# design.net
KiCad netlist of a schematic drawn in EAGLE
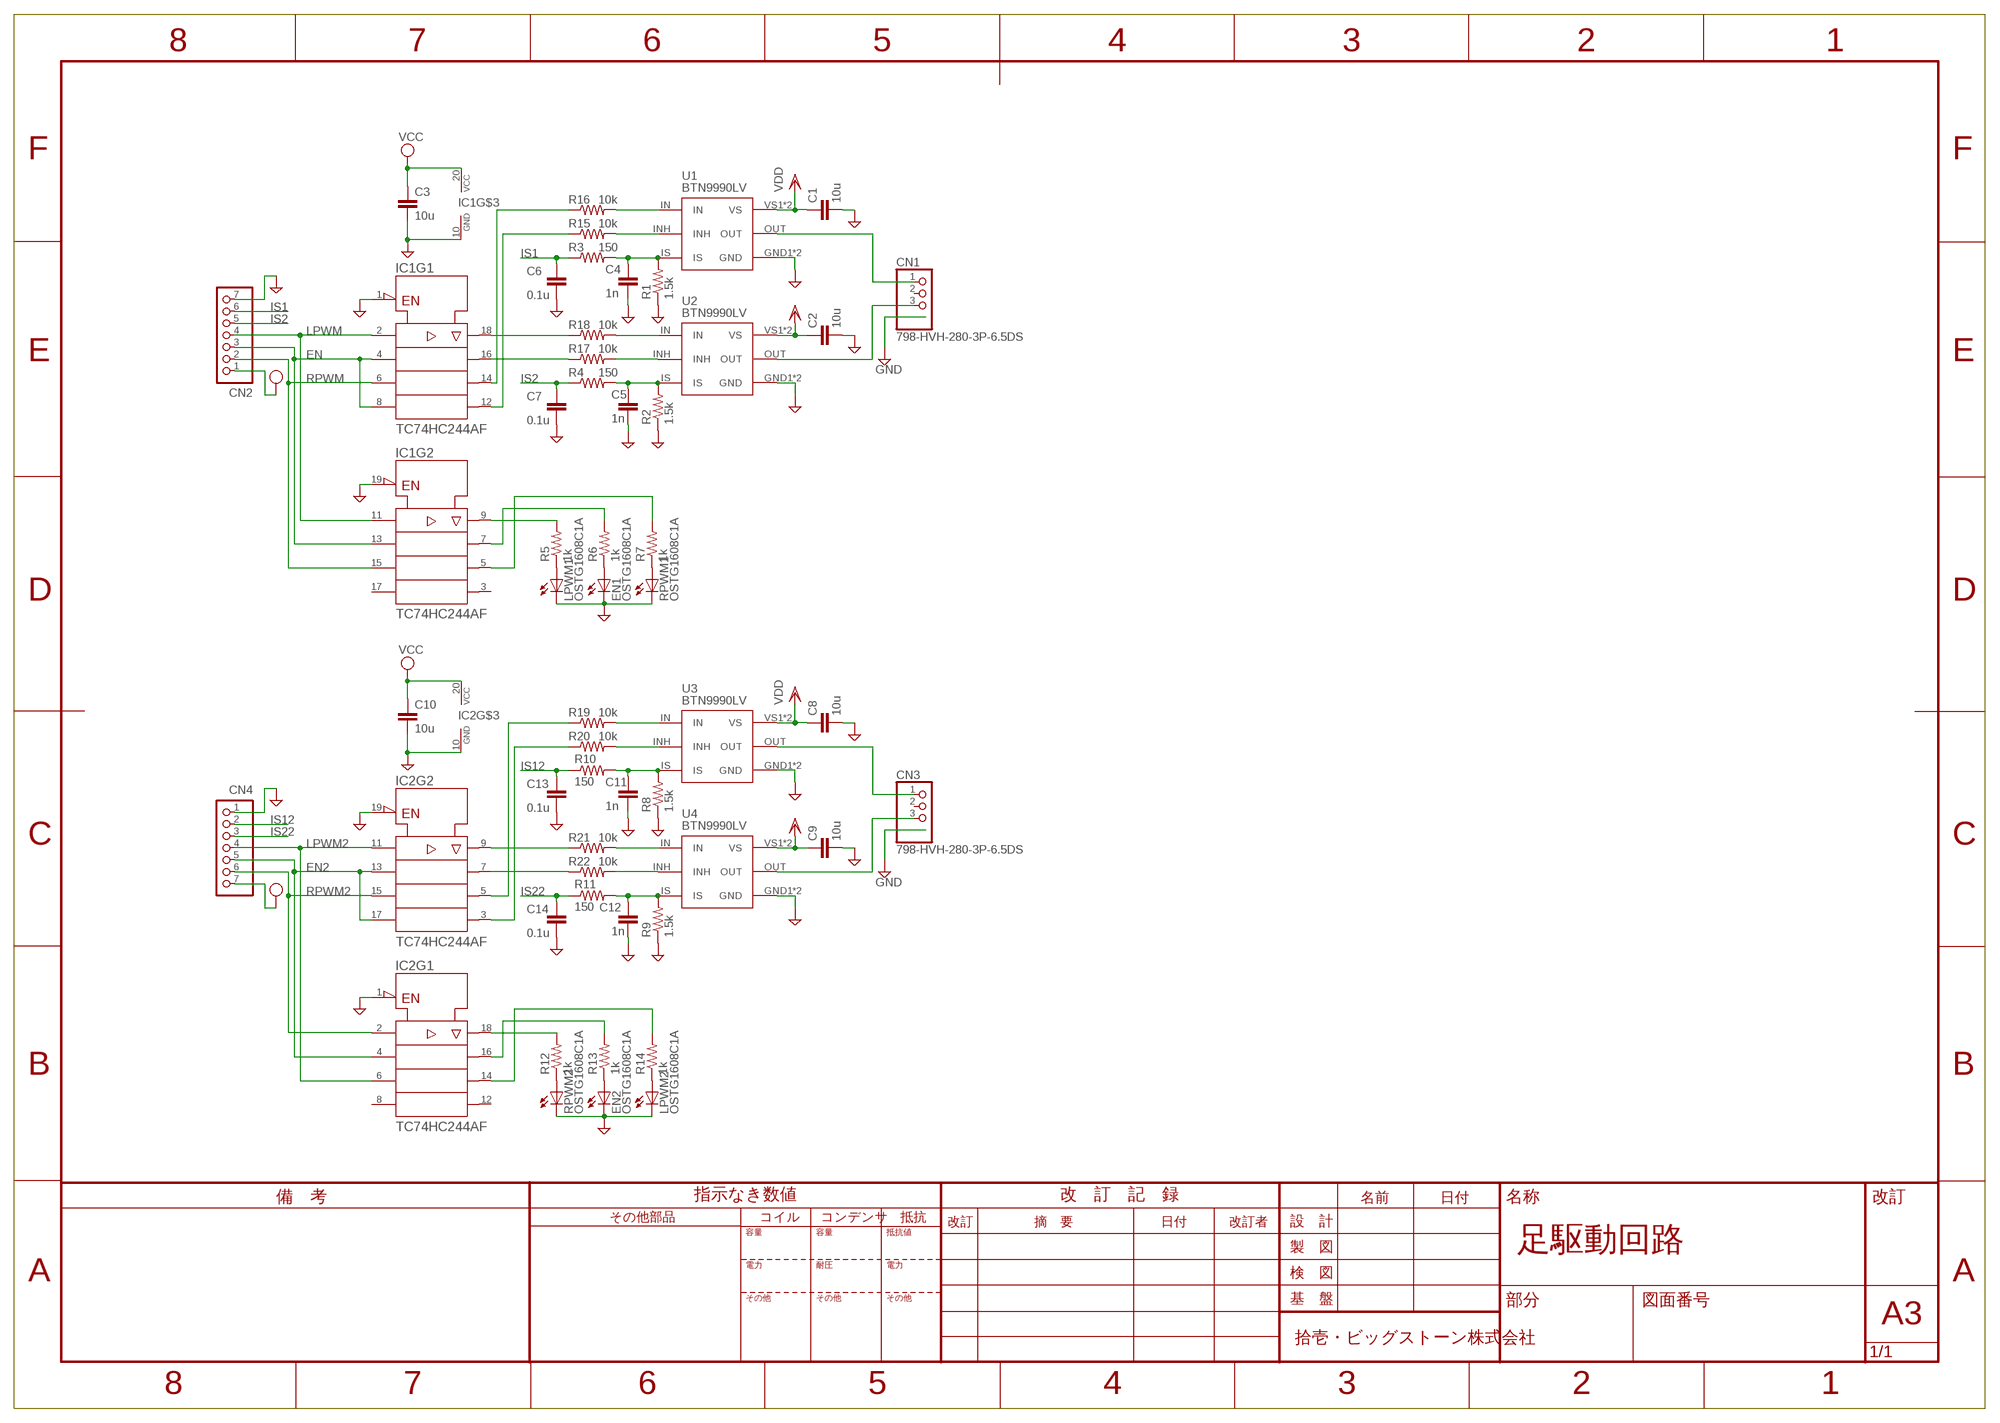
[diagram p0: schematic, sheet 1]

(export (version "E")
  (design (tool "Eeschema 10.0.6"))
  (components
    (comp (ref "C1")
      (value "10u")
      (footprint "eagle-import:C3216")
      (libsource (lib "eagle-import") (part "GCM?31CD71H106KE36K"))
    )
    (comp (ref "C2")
      (value "10u")
      (footprint "eagle-import:C3216")
      (libsource (lib "eagle-import") (part "GCM?31CD71H106KE36K"))
    )
    (comp (ref "C3")
      (value "10u")
      (footprint "eagle-import:C3216")
      (libsource (lib "eagle-import") (part "GCM?31CD71H106KE36K"))
    )
    (comp (ref "C4")
      (value "1n")
      (footprint "eagle-import:C1608")
      (libsource (lib "eagle-import") (part "GCM?188R91H102KA37D"))
    )
    (comp (ref "C5")
      (value "1n")
      (footprint "eagle-import:C1608")
      (libsource (lib "eagle-import") (part "GCM?188R91H102KA37D"))
    )
    (comp (ref "C6")
      (value "0.1u")
      (footprint "eagle-import:C1608")
      (libsource (lib "eagle-import") (part "GCM?188L81H104KA57D"))
    )
    (comp (ref "C7")
      (value "0.1u")
      (footprint "eagle-import:C1608")
      (libsource (lib "eagle-import") (part "GCM?188L81H104KA57D"))
    )
    (comp (ref "C8")
      (value "10u")
      (footprint "eagle-import:C3216")
      (libsource (lib "eagle-import") (part "GCM?31CD71H106KE36K"))
    )
    (comp (ref "C9")
      (value "10u")
      (footprint "eagle-import:C3216")
      (libsource (lib "eagle-import") (part "GCM?31CD71H106KE36K"))
    )
    (comp (ref "C10")
      (value "10u")
      (footprint "eagle-import:C3216")
      (libsource (lib "eagle-import") (part "GCM?31CD71H106KE36K"))
    )
    (comp (ref "C11")
      (value "1n")
      (footprint "eagle-import:C1608")
      (libsource (lib "eagle-import") (part "GCM?188R91H102KA37D"))
    )
    (comp (ref "C12")
      (value "1n")
      (footprint "eagle-import:C1608")
      (libsource (lib "eagle-import") (part "GCM?188R91H102KA37D"))
    )
    (comp (ref "C13")
      (value "0.1u")
      (footprint "eagle-import:C1608")
      (libsource (lib "eagle-import") (part "GCM?188L81H104KA57D"))
    )
    (comp (ref "C14")
      (value "0.1u")
      (footprint "eagle-import:C1608")
      (libsource (lib "eagle-import") (part "GCM?188L81H104KA57D"))
    )
    (comp (ref "CN1")
      (value "798-HVH-280-3P-6.5DS")
      (footprint "eagle-import:798-HVH-280-3P-6.5DS")
      (libsource (lib "eagle-import") (part "798-HVH-280-3P-6.5DS"))
    )
    (comp (ref "CN2")
      (value "B7B-XH-A")
      (footprint "eagle-import:B7B-XH-A")
      (libsource (lib "eagle-import") (part "B7B-XH-A"))
    )
    (comp (ref "CN3")
      (value "798-HVH-280-3P-6.5DS")
      (footprint "eagle-import:798-HVH-280-3P-6.5DS")
      (libsource (lib "eagle-import") (part "798-HVH-280-3P-6.5DS"))
    )
    (comp (ref "CN4")
      (value "B7B-XH-A")
      (footprint "eagle-import:B7B-XH-A")
      (libsource (lib "eagle-import") (part "B7B-XH-A"))
    )
    (comp (ref "EN1")
      (value "OSTG1608C1A")
      (footprint "eagle-import:LEDC1608X39N_G")
      (libsource (lib "eagle-import") (part "OSTG1608C1A"))
    )
    (comp (ref "EN2")
      (value "OSTG1608C1A")
      (footprint "eagle-import:LEDC1608X39N_G")
      (libsource (lib "eagle-import") (part "OSTG1608C1A"))
    )
    (comp (ref "IC1")
      (value "TC74HC244AF")
      (footprint "eagle-import:SOP20")
      (libsource (lib "eagle-import") (part "TC74HC244AF"))
    )
    (comp (ref "IC2")
      (value "TC74HC244AF")
      (footprint "eagle-import:SOP20")
      (libsource (lib "eagle-import") (part "TC74HC244AF"))
    )
    (comp (ref "LPWM1")
      (value "OSTG1608C1A")
      (footprint "eagle-import:LEDC1608X39N_G")
      (libsource (lib "eagle-import") (part "OSTG1608C1A"))
    )
    (comp (ref "LPWM2")
      (value "OSTG1608C1A")
      (footprint "eagle-import:LEDC1608X39N_G")
      (libsource (lib "eagle-import") (part "OSTG1608C1A"))
    )
    (comp (ref "R1")
      (value "1.5k")
      (footprint "eagle-import:R0603")
      (libsource (lib "eagle-import") (part "R1608"))
    )
    (comp (ref "R2")
      (value "1.5k")
      (footprint "eagle-import:R0603")
      (libsource (lib "eagle-import") (part "R1608"))
    )
    (comp (ref "R3")
      (value "150")
      (footprint "eagle-import:R0603")
      (libsource (lib "eagle-import") (part "R1608"))
    )
    (comp (ref "R4")
      (value "150")
      (footprint "eagle-import:R0603")
      (libsource (lib "eagle-import") (part "R1608"))
    )
    (comp (ref "R5")
      (value "1k")
      (footprint "eagle-import:R0603")
      (libsource (lib "eagle-import") (part "R1608"))
    )
    (comp (ref "R6")
      (value "1k")
      (footprint "eagle-import:R0603")
      (libsource (lib "eagle-import") (part "R1608"))
    )
    (comp (ref "R7")
      (value "1k")
      (footprint "eagle-import:R0603")
      (libsource (lib "eagle-import") (part "R1608"))
    )
    (comp (ref "R8")
      (value "1.5k")
      (footprint "eagle-import:R0603")
      (libsource (lib "eagle-import") (part "R1608"))
    )
    (comp (ref "R9")
      (value "1.5k")
      (footprint "eagle-import:R0603")
      (libsource (lib "eagle-import") (part "R1608"))
    )
    (comp (ref "R10")
      (value "150")
      (footprint "eagle-import:R0603")
      (libsource (lib "eagle-import") (part "R1608"))
    )
    (comp (ref "R11")
      (value "150")
      (footprint "eagle-import:R0603")
      (libsource (lib "eagle-import") (part "R1608"))
    )
    (comp (ref "R12")
      (value "1k")
      (footprint "eagle-import:R0603")
      (libsource (lib "eagle-import") (part "R1608"))
    )
    (comp (ref "R13")
      (value "1k")
      (footprint "eagle-import:R0603")
      (libsource (lib "eagle-import") (part "R1608"))
    )
    (comp (ref "R14")
      (value "1k")
      (footprint "eagle-import:R0603")
      (libsource (lib "eagle-import") (part "R1608"))
    )
    (comp (ref "R15")
      (value "10k")
      (footprint "eagle-import:R1608")
      (libsource (lib "eagle-import") (part "RC0603J10K"))
    )
    (comp (ref "R16")
      (value "10k")
      (footprint "eagle-import:R1608")
      (libsource (lib "eagle-import") (part "RC0603J10K"))
    )
    (comp (ref "R17")
      (value "10k")
      (footprint "eagle-import:R1608")
      (libsource (lib "eagle-import") (part "RC0603J10K"))
    )
    (comp (ref "R18")
      (value "10k")
      (footprint "eagle-import:R1608")
      (libsource (lib "eagle-import") (part "RC0603J10K"))
    )
    (comp (ref "R19")
      (value "10k")
      (footprint "eagle-import:R1608")
      (libsource (lib "eagle-import") (part "RC0603J10K"))
    )
    (comp (ref "R20")
      (value "10k")
      (footprint "eagle-import:R1608")
      (libsource (lib "eagle-import") (part "RC0603J10K"))
    )
    (comp (ref "R21")
      (value "10k")
      (footprint "eagle-import:R1608")
      (libsource (lib "eagle-import") (part "RC0603J10K"))
    )
    (comp (ref "R22")
      (value "10k")
      (footprint "eagle-import:R1608")
      (libsource (lib "eagle-import") (part "RC0603J10K"))
    )
    (comp (ref "RPWM1")
      (value "OSTG1608C1A")
      (footprint "eagle-import:LEDC1608X39N_G")
      (libsource (lib "eagle-import") (part "OSTG1608C1A"))
    )
    (comp (ref "RPWM2")
      (value "OSTG1608C1A")
      (footprint "eagle-import:LEDC1608X39N_G")
      (libsource (lib "eagle-import") (part "OSTG1608C1A"))
    )
    (comp (ref "U1")
      (value "BTN9990LV")
      (footprint "eagle-import:BTN9990LV")
      (libsource (lib "eagle-import") (part "BTN9990LV"))
    )
    (comp (ref "U2")
      (value "BTN9990LV")
      (footprint "eagle-import:BTN9990LV")
      (libsource (lib "eagle-import") (part "BTN9990LV"))
    )
    (comp (ref "U3")
      (value "BTN9990LV")
      (footprint "eagle-import:BTN9990LV")
      (libsource (lib "eagle-import") (part "BTN9990LV"))
    )
    (comp (ref "U4")
      (value "BTN9990LV")
      (footprint "eagle-import:BTN9990LV")
      (libsource (lib "eagle-import") (part "BTN9990LV"))
    )
  )
  (nets
    (net (code "1") (name "/EN") (class "Default")
      (node (ref "CN2") (pin "3") (pinfunction "3_3") (pintype "passive"))
      (node (ref "IC1") (pin "13") (pinfunction "A2_13") (pintype "input"))
      (node (ref "IC1") (pin "4") (pinfunction "A2_4") (pintype "input"))
      (node (ref "IC1") (pin "8") (pinfunction "A4_8") (pintype "input"))
    )
    (net (code "2") (name "/EN2") (class "Default")
      (node (ref "CN4") (pin "5") (pinfunction "5_5") (pintype "passive"))
      (node (ref "IC2") (pin "13") (pinfunction "A2_13") (pintype "input"))
      (node (ref "IC2") (pin "17") (pinfunction "A4_17") (pintype "input"))
      (node (ref "IC2") (pin "4") (pinfunction "A2_4") (pintype "input"))
    )
    (net (code "3") (name "/IS1") (class "Default")
      (node (ref "C6") (pin "1") (pinfunction "1_1") (pintype "passive"))
      (node (ref "CN2") (pin "6") (pinfunction "6_6") (pintype "passive"))
      (node (ref "R3") (pin "1") (pinfunction "1_1") (pintype "passive"))
    )
    (net (code "4") (name "/IS2") (class "Default")
      (node (ref "C7") (pin "1") (pinfunction "1_1") (pintype "passive"))
      (node (ref "CN2") (pin "5") (pinfunction "5_5") (pintype "passive"))
      (node (ref "R4") (pin "1") (pinfunction "1_1") (pintype "passive"))
    )
    (net (code "5") (name "/IS12") (class "Default")
      (node (ref "C13") (pin "1") (pinfunction "1_1") (pintype "passive"))
      (node (ref "CN4") (pin "2") (pinfunction "2_2") (pintype "passive"))
      (node (ref "R10") (pin "1") (pinfunction "1_1") (pintype "passive"))
    )
    (net (code "6") (name "/IS22") (class "Default")
      (node (ref "C14") (pin "1") (pinfunction "1_1") (pintype "passive"))
      (node (ref "CN4") (pin "3") (pinfunction "3_3") (pintype "passive"))
      (node (ref "R11") (pin "1") (pinfunction "1_1") (pintype "passive"))
    )
    (net (code "7") (name "/LPWM") (class "Default")
      (node (ref "CN2") (pin "4") (pinfunction "4_4") (pintype "passive"))
      (node (ref "IC1") (pin "11") (pinfunction "A1_11") (pintype "input"))
      (node (ref "IC1") (pin "2") (pinfunction "A1_2") (pintype "input"))
    )
    (net (code "8") (name "/LPWM2") (class "Default")
      (node (ref "CN4") (pin "4") (pinfunction "4_4") (pintype "passive"))
      (node (ref "IC2") (pin "11") (pinfunction "A1_11") (pintype "input"))
      (node (ref "IC2") (pin "6") (pinfunction "A3_6") (pintype "input"))
    )
    (net (code "9") (name "/RPWM") (class "Default")
      (node (ref "CN2") (pin "2") (pinfunction "2_2") (pintype "passive"))
      (node (ref "IC1") (pin "15") (pinfunction "A3_15") (pintype "input"))
      (node (ref "IC1") (pin "6") (pinfunction "A3_6") (pintype "input"))
    )
    (net (code "10") (name "/RPWM2") (class "Default")
      (node (ref "CN4") (pin "6") (pinfunction "6_6") (pintype "passive"))
      (node (ref "IC2") (pin "15") (pinfunction "A3_15") (pintype "input"))
      (node (ref "IC2") (pin "2") (pinfunction "A1_2") (pintype "input"))
    )
    (net (code "11") (name "GND") (class "Default")
      (node (ref "C1") (pin "2") (pinfunction "2_2") (pintype "passive"))
      (node (ref "C10") (pin "2") (pinfunction "2_2") (pintype "passive"))
      (node (ref "C11") (pin "2") (pinfunction "2_2") (pintype "passive"))
      (node (ref "C12") (pin "2") (pinfunction "2_2") (pintype "passive"))
      (node (ref "C13") (pin "2") (pinfunction "2_2") (pintype "passive"))
      (node (ref "C14") (pin "2") (pinfunction "2_2") (pintype "passive"))
      (node (ref "C2") (pin "2") (pinfunction "2_2") (pintype "passive"))
      (node (ref "C3") (pin "2") (pinfunction "2_2") (pintype "passive"))
      (node (ref "C4") (pin "2") (pinfunction "2_2") (pintype "passive"))
      (node (ref "C5") (pin "2") (pinfunction "2_2") (pintype "passive"))
      (node (ref "C6") (pin "2") (pinfunction "2_2") (pintype "passive"))
      (node (ref "C7") (pin "2") (pinfunction "2_2") (pintype "passive"))
      (node (ref "C8") (pin "2") (pinfunction "2_2") (pintype "passive"))
      (node (ref "C9") (pin "2") (pinfunction "2_2") (pintype "passive"))
      (node (ref "CN1") (pin "P$1") (pinfunction "P$1_P$1") (pintype "bidirectional"))
      (node (ref "CN1") (pin "P$2") (pinfunction "P$1_P$2") (pintype "bidirectional"))
      (node (ref "CN1") (pin "P$3") (pinfunction "P$1_P$3") (pintype "bidirectional"))
      (node (ref "CN1") (pin "P$4") (pinfunction "P$1_P$4") (pintype "bidirectional"))
      (node (ref "CN2") (pin "7") (pinfunction "7_7") (pintype "passive"))
      (node (ref "CN3") (pin "P$1") (pinfunction "P$1_P$1") (pintype "bidirectional"))
      (node (ref "CN3") (pin "P$2") (pinfunction "P$1_P$2") (pintype "bidirectional"))
      (node (ref "CN3") (pin "P$3") (pinfunction "P$1_P$3") (pintype "bidirectional"))
      (node (ref "CN3") (pin "P$4") (pinfunction "P$1_P$4") (pintype "bidirectional"))
      (node (ref "CN4") (pin "1") (pinfunction "1_1") (pintype "passive"))
      (node (ref "EN1") (pin "K") (pinfunction "C_K") (pintype "passive"))
      (node (ref "EN2") (pin "K") (pinfunction "C_K") (pintype "passive"))
      (node (ref "IC1") (pin "1") (pinfunction "~{G}_1") (pintype "input"))
      (node (ref "IC1") (pin "10") (pinfunction "GND_10") (pintype "power_in"))
      (node (ref "IC1") (pin "19") (pinfunction "~{G}_19") (pintype "input"))
      (node (ref "IC2") (pin "1") (pinfunction "~{G}_1") (pintype "input"))
      (node (ref "IC2") (pin "10") (pinfunction "GND_10") (pintype "power_in"))
      (node (ref "IC2") (pin "19") (pinfunction "~{G}_19") (pintype "input"))
      (node (ref "LPWM1") (pin "K") (pinfunction "C_K") (pintype "passive"))
      (node (ref "LPWM2") (pin "K") (pinfunction "C_K") (pintype "passive"))
      (node (ref "R1") (pin "1") (pinfunction "1_1") (pintype "passive"))
      (node (ref "R2") (pin "1") (pinfunction "1_1") (pintype "passive"))
      (node (ref "R8") (pin "1") (pinfunction "1_1") (pintype "passive"))
      (node (ref "R9") (pin "1") (pinfunction "1_1") (pintype "passive"))
      (node (ref "RPWM1") (pin "K") (pinfunction "C_K") (pintype "passive"))
      (node (ref "RPWM2") (pin "K") (pinfunction "C_K") (pintype "passive"))
      (node (ref "U1") (pin "GND1") (pinfunction "GND_GND1") (pintype "bidirectional"))
      (node (ref "U1") (pin "GND2") (pinfunction "GND_GND2") (pintype "bidirectional"))
      (node (ref "U2") (pin "GND1") (pinfunction "GND_GND1") (pintype "bidirectional"))
      (node (ref "U2") (pin "GND2") (pinfunction "GND_GND2") (pintype "bidirectional"))
      (node (ref "U3") (pin "GND1") (pinfunction "GND_GND1") (pintype "bidirectional"))
      (node (ref "U3") (pin "GND2") (pinfunction "GND_GND2") (pintype "bidirectional"))
      (node (ref "U4") (pin "GND1") (pinfunction "GND_GND1") (pintype "bidirectional"))
      (node (ref "U4") (pin "GND2") (pinfunction "GND_GND2") (pintype "bidirectional"))
    )
    (net (code "12") (name "Net-(C4-Pad1)") (class "Default")
      (node (ref "C4") (pin "1") (pinfunction "1_1") (pintype "passive"))
      (node (ref "R1") (pin "2") (pinfunction "2_2") (pintype "passive"))
      (node (ref "R3") (pin "2") (pinfunction "2_2") (pintype "passive"))
      (node (ref "U1") (pin "IS") (pinfunction "IS_IS") (pintype "bidirectional"))
    )
    (net (code "13") (name "Net-(C5-Pad1)") (class "Default")
      (node (ref "C5") (pin "1") (pinfunction "1_1") (pintype "passive"))
      (node (ref "R2") (pin "2") (pinfunction "2_2") (pintype "passive"))
      (node (ref "R4") (pin "2") (pinfunction "2_2") (pintype "passive"))
      (node (ref "U2") (pin "IS") (pinfunction "IS_IS") (pintype "bidirectional"))
    )
    (net (code "14") (name "Net-(C11-Pad1)") (class "Default")
      (node (ref "C11") (pin "1") (pinfunction "1_1") (pintype "passive"))
      (node (ref "R10") (pin "2") (pinfunction "2_2") (pintype "passive"))
      (node (ref "R8") (pin "2") (pinfunction "2_2") (pintype "passive"))
      (node (ref "U3") (pin "IS") (pinfunction "IS_IS") (pintype "bidirectional"))
    )
    (net (code "15") (name "Net-(C12-Pad1)") (class "Default")
      (node (ref "C12") (pin "1") (pinfunction "1_1") (pintype "passive"))
      (node (ref "R11") (pin "2") (pinfunction "2_2") (pintype "passive"))
      (node (ref "R9") (pin "2") (pinfunction "2_2") (pintype "passive"))
      (node (ref "U4") (pin "IS") (pinfunction "IS_IS") (pintype "bidirectional"))
    )
    (net (code "16") (name "Net-(CN1-Pad1)") (class "Default")
      (node (ref "CN1") (pin "1") (pinfunction "1_1") (pintype "passive"))
      (node (ref "U1") (pin "OUT") (pinfunction "OUT_OUT") (pintype "bidirectional"))
    )
    (net (code "17") (name "Net-(CN1-Pad3)") (class "Default")
      (node (ref "CN1") (pin "3") (pinfunction "3_3") (pintype "passive"))
      (node (ref "U2") (pin "OUT") (pinfunction "OUT_OUT") (pintype "bidirectional"))
    )
    (net (code "18") (name "Net-(CN3-Pad1)") (class "Default")
      (node (ref "CN3") (pin "1") (pinfunction "1_1") (pintype "passive"))
      (node (ref "U3") (pin "OUT") (pinfunction "OUT_OUT") (pintype "bidirectional"))
    )
    (net (code "19") (name "Net-(CN3-Pad3)") (class "Default")
      (node (ref "CN3") (pin "3") (pinfunction "3_3") (pintype "passive"))
      (node (ref "U4") (pin "OUT") (pinfunction "OUT_OUT") (pintype "bidirectional"))
    )
    (net (code "20") (name "Net-(EN1-PadA)") (class "Default")
      (node (ref "EN1") (pin "A") (pinfunction "A_A") (pintype "passive"))
      (node (ref "R6") (pin "1") (pinfunction "1_1") (pintype "passive"))
    )
    (net (code "21") (name "Net-(EN2-PadA)") (class "Default")
      (node (ref "EN2") (pin "A") (pinfunction "A_A") (pintype "passive"))
      (node (ref "R13") (pin "1") (pinfunction "1_1") (pintype "passive"))
    )
    (net (code "22") (name "Net-(IC1B-Y1)") (class "Default")
      (node (ref "IC1") (pin "18") (pinfunction "Y1_18") (pintype "tri_state"))
      (node (ref "R18") (pin "1") (pinfunction "1_1") (pintype "passive"))
    )
    (net (code "23") (name "Net-(IC1B-Y2)") (class "Default")
      (node (ref "IC1") (pin "16") (pinfunction "Y2_16") (pintype "tri_state"))
      (node (ref "R17") (pin "1") (pinfunction "1_1") (pintype "passive"))
    )
    (net (code "24") (name "Net-(IC1B-Y3)") (class "Default")
      (node (ref "IC1") (pin "14") (pinfunction "Y3_14") (pintype "tri_state"))
      (node (ref "R16") (pin "1") (pinfunction "1_1") (pintype "passive"))
    )
    (net (code "25") (name "Net-(IC1B-Y4)") (class "Default")
      (node (ref "IC1") (pin "12") (pinfunction "Y4_12") (pintype "tri_state"))
      (node (ref "R15") (pin "1") (pinfunction "1_1") (pintype "passive"))
    )
    (net (code "26") (name "Net-(IC1C-Y1)") (class "Default")
      (node (ref "IC1") (pin "9") (pinfunction "Y1_9") (pintype "tri_state"))
      (node (ref "R5") (pin "2") (pinfunction "2_2") (pintype "passive"))
    )
    (net (code "27") (name "Net-(IC1C-Y2)") (class "Default")
      (node (ref "IC1") (pin "7") (pinfunction "Y2_7") (pintype "tri_state"))
      (node (ref "R6") (pin "2") (pinfunction "2_2") (pintype "passive"))
    )
    (net (code "28") (name "Net-(IC1C-Y3)") (class "Default")
      (node (ref "IC1") (pin "5") (pinfunction "Y3_5") (pintype "tri_state"))
      (node (ref "R7") (pin "2") (pinfunction "2_2") (pintype "passive"))
    )
    (net (code "29") (name "Net-(IC2B-Y1)") (class "Default")
      (node (ref "IC2") (pin "18") (pinfunction "Y1_18") (pintype "tri_state"))
      (node (ref "R12") (pin "2") (pinfunction "2_2") (pintype "passive"))
    )
    (net (code "30") (name "Net-(IC2B-Y2)") (class "Default")
      (node (ref "IC2") (pin "16") (pinfunction "Y2_16") (pintype "tri_state"))
      (node (ref "R13") (pin "2") (pinfunction "2_2") (pintype "passive"))
    )
    (net (code "31") (name "Net-(IC2B-Y3)") (class "Default")
      (node (ref "IC2") (pin "14") (pinfunction "Y3_14") (pintype "tri_state"))
      (node (ref "R14") (pin "2") (pinfunction "2_2") (pintype "passive"))
    )
    (net (code "32") (name "Net-(IC2C-Y1)") (class "Default")
      (node (ref "IC2") (pin "9") (pinfunction "Y1_9") (pintype "tri_state"))
      (node (ref "R21") (pin "1") (pinfunction "1_1") (pintype "passive"))
    )
    (net (code "33") (name "Net-(IC2C-Y2)") (class "Default")
      (node (ref "IC2") (pin "7") (pinfunction "Y2_7") (pintype "tri_state"))
      (node (ref "R22") (pin "1") (pinfunction "1_1") (pintype "passive"))
    )
    (net (code "34") (name "Net-(IC2C-Y3)") (class "Default")
      (node (ref "IC2") (pin "5") (pinfunction "Y3_5") (pintype "tri_state"))
      (node (ref "R19") (pin "1") (pinfunction "1_1") (pintype "passive"))
    )
    (net (code "35") (name "Net-(IC2C-Y4)") (class "Default")
      (node (ref "IC2") (pin "3") (pinfunction "Y4_3") (pintype "tri_state"))
      (node (ref "R20") (pin "1") (pinfunction "1_1") (pintype "passive"))
    )
    (net (code "36") (name "Net-(LPWM1-PadA)") (class "Default")
      (node (ref "LPWM1") (pin "A") (pinfunction "A_A") (pintype "passive"))
      (node (ref "R5") (pin "1") (pinfunction "1_1") (pintype "passive"))
    )
    (net (code "37") (name "Net-(LPWM2-PadA)") (class "Default")
      (node (ref "LPWM2") (pin "A") (pinfunction "A_A") (pintype "passive"))
      (node (ref "R14") (pin "1") (pinfunction "1_1") (pintype "passive"))
    )
    (net (code "38") (name "Net-(R7-Pad1)") (class "Default")
      (node (ref "R7") (pin "1") (pinfunction "1_1") (pintype "passive"))
      (node (ref "RPWM1") (pin "A") (pinfunction "A_A") (pintype "passive"))
    )
    (net (code "39") (name "Net-(R12-Pad1)") (class "Default")
      (node (ref "R12") (pin "1") (pinfunction "1_1") (pintype "passive"))
      (node (ref "RPWM2") (pin "A") (pinfunction "A_A") (pintype "passive"))
    )
    (net (code "40") (name "Net-(R15-Pad2)") (class "Default")
      (node (ref "R15") (pin "2") (pinfunction "2_2") (pintype "passive"))
      (node (ref "U1") (pin "INH") (pinfunction "INH_INH") (pintype "bidirectional"))
    )
    (net (code "41") (name "Net-(R16-Pad2)") (class "Default")
      (node (ref "R16") (pin "2") (pinfunction "2_2") (pintype "passive"))
      (node (ref "U1") (pin "IN") (pinfunction "IN_IN") (pintype "bidirectional"))
    )
    (net (code "42") (name "Net-(R17-Pad2)") (class "Default")
      (node (ref "R17") (pin "2") (pinfunction "2_2") (pintype "passive"))
      (node (ref "U2") (pin "INH") (pinfunction "INH_INH") (pintype "bidirectional"))
    )
    (net (code "43") (name "Net-(R18-Pad2)") (class "Default")
      (node (ref "R18") (pin "2") (pinfunction "2_2") (pintype "passive"))
      (node (ref "U2") (pin "IN") (pinfunction "IN_IN") (pintype "bidirectional"))
    )
    (net (code "44") (name "Net-(R19-Pad2)") (class "Default")
      (node (ref "R19") (pin "2") (pinfunction "2_2") (pintype "passive"))
      (node (ref "U3") (pin "IN") (pinfunction "IN_IN") (pintype "bidirectional"))
    )
    (net (code "45") (name "Net-(R20-Pad2)") (class "Default")
      (node (ref "R20") (pin "2") (pinfunction "2_2") (pintype "passive"))
      (node (ref "U3") (pin "INH") (pinfunction "INH_INH") (pintype "bidirectional"))
    )
    (net (code "46") (name "Net-(R21-Pad2)") (class "Default")
      (node (ref "R21") (pin "2") (pinfunction "2_2") (pintype "passive"))
      (node (ref "U4") (pin "IN") (pinfunction "IN_IN") (pintype "bidirectional"))
    )
    (net (code "47") (name "Net-(R22-Pad2)") (class "Default")
      (node (ref "R22") (pin "2") (pinfunction "2_2") (pintype "passive"))
      (node (ref "U4") (pin "INH") (pinfunction "INH_INH") (pintype "bidirectional"))
    )
    (net (code "48") (name "VCC") (class "Default")
      (node (ref "C10") (pin "1") (pinfunction "1_1") (pintype "passive"))
      (node (ref "C3") (pin "1") (pinfunction "1_1") (pintype "passive"))
      (node (ref "CN2") (pin "1") (pinfunction "1_1") (pintype "passive"))
      (node (ref "CN4") (pin "7") (pinfunction "7_7") (pintype "passive"))
      (node (ref "IC1") (pin "20") (pinfunction "VCC_20") (pintype "power_in"))
      (node (ref "IC2") (pin "20") (pinfunction "VCC_20") (pintype "power_in"))
    )
    (net (code "49") (name "VDD") (class "Default")
      (node (ref "C1") (pin "1") (pinfunction "1_1") (pintype "passive"))
      (node (ref "C2") (pin "1") (pinfunction "1_1") (pintype "passive"))
      (node (ref "C8") (pin "1") (pinfunction "1_1") (pintype "passive"))
      (node (ref "C9") (pin "1") (pinfunction "1_1") (pintype "passive"))
      (node (ref "U1") (pin "VS1") (pinfunction "VS_VS1") (pintype "bidirectional"))
      (node (ref "U1") (pin "VS2") (pinfunction "VS_VS2") (pintype "bidirectional"))
      (node (ref "U2") (pin "VS1") (pinfunction "VS_VS1") (pintype "bidirectional"))
      (node (ref "U2") (pin "VS2") (pinfunction "VS_VS2") (pintype "bidirectional"))
      (node (ref "U3") (pin "VS1") (pinfunction "VS_VS1") (pintype "bidirectional"))
      (node (ref "U3") (pin "VS2") (pinfunction "VS_VS2") (pintype "bidirectional"))
      (node (ref "U4") (pin "VS1") (pinfunction "VS_VS1") (pintype "bidirectional"))
      (node (ref "U4") (pin "VS2") (pinfunction "VS_VS2") (pintype "bidirectional"))
    )
    (net (code "50") (name "unconnected-(CN1-Pad2)") (class "Default")
      (node (ref "CN1") (pin "2") (pinfunction "2_2") (pintype "passive"))
    )
    (net (code "51") (name "unconnected-(CN3-Pad2)") (class "Default")
      (node (ref "CN3") (pin "2") (pinfunction "2_2") (pintype "passive"))
    )
    (net (code "52") (name "unconnected-(IC1C-A4-Pad17)") (class "Default")
      (node (ref "IC1") (pin "17") (pinfunction "A4_17") (pintype "input"))
    )
    (net (code "53") (name "unconnected-(IC1C-Y4-Pad3)") (class "Default")
      (node (ref "IC1") (pin "3") (pinfunction "Y4_3") (pintype "tri_state"))
    )
    (net (code "54") (name "unconnected-(IC2B-A4-Pad8)") (class "Default")
      (node (ref "IC2") (pin "8") (pinfunction "A4_8") (pintype "input"))
    )
    (net (code "55") (name "unconnected-(IC2B-Y4-Pad12)") (class "Default")
      (node (ref "IC2") (pin "12") (pinfunction "Y4_12") (pintype "tri_state"))
    )
  )
)
